# AND.net
KiCad netlist of a schematic drawn in EAGLE
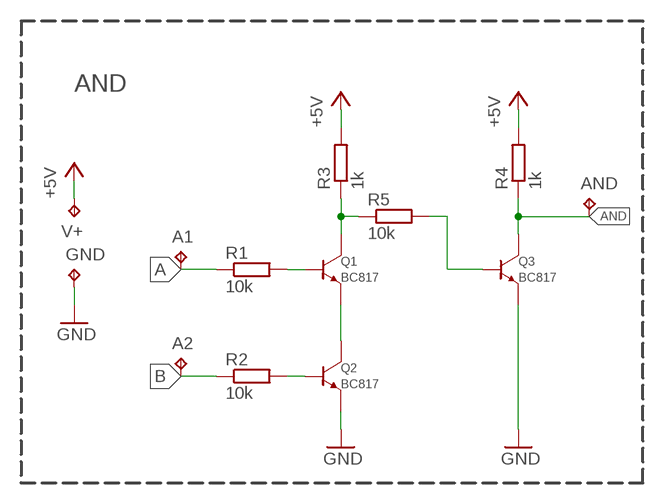
[diagram p0: schematic, sheet 1]

(export (version "E")
  (design (tool "Eeschema 10.0.6"))
  (components
    (comp (ref "A1")
      (value "TPTP07R")
      (footprint "eagle-import:TP07R")
      (libsource (lib "eagle-import") (part "TPTP07R"))
    )
    (comp (ref "A2")
      (value "TPTP07R")
      (footprint "eagle-import:TP07R")
      (libsource (lib "eagle-import") (part "TPTP07R"))
    )
    (comp (ref "AND")
      (value "TPTP07R")
      (footprint "eagle-import:TP07R")
      (libsource (lib "eagle-import") (part "TPTP07R"))
    )
    (comp (ref "GND")
      (value "TPTP07R")
      (footprint "eagle-import:TP07R")
      (libsource (lib "eagle-import") (part "TPTP07R"))
    )
    (comp (ref "Q1")
      (value "BC817")
      (footprint "eagle-import:SOT23")
      (libsource (lib "eagle-import") (part "TRANSISTOR-NPN-GENERIC-SOT23-BECDEFAULT"))
    )
    (comp (ref "Q2")
      (value "BC817")
      (footprint "eagle-import:SOT23")
      (libsource (lib "eagle-import") (part "TRANSISTOR-NPN-GENERIC-SOT23-BECDEFAULT"))
    )
    (comp (ref "Q3")
      (value "BC817")
      (footprint "eagle-import:SOT23")
      (libsource (lib "eagle-import") (part "TRANSISTOR-NPN-GENERIC-SOT23-BECDEFAULT"))
    )
    (comp (ref "R1")
      (value "10k")
      (footprint "eagle-import:R0603")
      (libsource (lib "eagle-import") (part "R-EU_R0603"))
    )
    (comp (ref "R2")
      (value "10k")
      (footprint "eagle-import:R0603")
      (libsource (lib "eagle-import") (part "R-EU_R0603"))
    )
    (comp (ref "R3")
      (value "1k")
      (footprint "eagle-import:R0603")
      (libsource (lib "eagle-import") (part "R-EU_R0603"))
    )
    (comp (ref "R4")
      (value "1k")
      (footprint "eagle-import:R0603")
      (libsource (lib "eagle-import") (part "R-EU_R0603"))
    )
    (comp (ref "R5")
      (value "10k")
      (footprint "eagle-import:R0603")
      (libsource (lib "eagle-import") (part "R-EU_R0603"))
    )
    (comp (ref "V+")
      (value "TPTP07R")
      (footprint "eagle-import:TP07R")
      (libsource (lib "eagle-import") (part "TPTP07R"))
    )
  )
  (nets
    (net (code "1") (name "+5V") (class "Default")
      (node (ref "R3") (pin "2") (pinfunction "2_2") (pintype "passive"))
      (node (ref "R4") (pin "2") (pinfunction "2_2") (pintype "passive"))
      (node (ref "V+") (pin "TP") (pinfunction "TP_TP") (pintype "input"))
    )
    (net (code "2") (name "A") (class "Default")
      (node (ref "A1") (pin "TP") (pinfunction "TP_TP") (pintype "input"))
      (node (ref "R1") (pin "1") (pinfunction "1_1") (pintype "passive"))
    )
    (net (code "3") (name "AND") (class "Default")
      (node (ref "AND") (pin "TP") (pinfunction "TP_TP") (pintype "input"))
      (node (ref "Q3") (pin "P$3") (pinfunction "COLLECTOR_P$3") (pintype "bidirectional"))
      (node (ref "R4") (pin "1") (pinfunction "1_1") (pintype "passive"))
    )
    (net (code "4") (name "B") (class "Default")
      (node (ref "A2") (pin "TP") (pinfunction "TP_TP") (pintype "input"))
      (node (ref "R2") (pin "1") (pinfunction "1_1") (pintype "passive"))
    )
    (net (code "5") (name "GND") (class "Default")
      (node (ref "GND") (pin "TP") (pinfunction "TP_TP") (pintype "input"))
      (node (ref "Q2") (pin "P$2") (pinfunction "EMITTER_P$2") (pintype "bidirectional"))
      (node (ref "Q3") (pin "P$2") (pinfunction "EMITTER_P$2") (pintype "bidirectional"))
    )
    (net (code "6") (name "Net-(Q1-BASE)") (class "Default")
      (node (ref "Q1") (pin "P$1") (pinfunction "BASE_P$1") (pintype "bidirectional"))
      (node (ref "R1") (pin "2") (pinfunction "2_2") (pintype "passive"))
    )
    (net (code "7") (name "Net-(Q1-COLLECTOR)") (class "Default")
      (node (ref "Q1") (pin "P$3") (pinfunction "COLLECTOR_P$3") (pintype "bidirectional"))
      (node (ref "R3") (pin "1") (pinfunction "1_1") (pintype "passive"))
      (node (ref "R5") (pin "1") (pinfunction "1_1") (pintype "passive"))
    )
    (net (code "8") (name "Net-(Q1-EMITTER)") (class "Default")
      (node (ref "Q1") (pin "P$2") (pinfunction "EMITTER_P$2") (pintype "bidirectional"))
      (node (ref "Q2") (pin "P$3") (pinfunction "COLLECTOR_P$3") (pintype "bidirectional"))
    )
    (net (code "9") (name "Net-(Q2-BASE)") (class "Default")
      (node (ref "Q2") (pin "P$1") (pinfunction "BASE_P$1") (pintype "bidirectional"))
      (node (ref "R2") (pin "2") (pinfunction "2_2") (pintype "passive"))
    )
    (net (code "10") (name "Net-(Q3-BASE)") (class "Default")
      (node (ref "Q3") (pin "P$1") (pinfunction "BASE_P$1") (pintype "bidirectional"))
      (node (ref "R5") (pin "2") (pinfunction "2_2") (pintype "passive"))
    )
  )
)
